# PNPdriver.net
KiCad netlist of a schematic drawn in Altium Designer
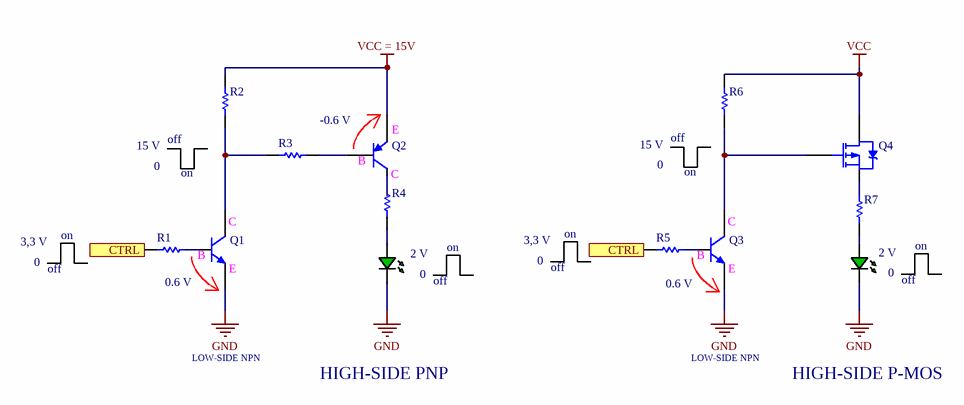
[diagram p0: PNPdriver.SchDoc]

(export (version "E")
  (design (tool "Eeschema 10.0.6"))
  (components
    (comp (ref "Q1")
      (value "2N3904")
      (footprint "TO-92A")
      (description "NPN General Purpose Amplifier")
      (fields (field (name "PUBLISHER") "Altium Limited"))
      (libsource (lib "Miscellaneous Devices") (part "2N3904"))
    )
    (comp (ref "Q2")
      (value "2N3906")
      (footprint "TO-92A")
      (description "PNP General Purpose Amplifier")
      (fields (field (name "PUBLISHER") "Altium Limited"))
      (libsource (lib "Miscellaneous Devices") (part "2N3906"))
    )
    (comp (ref "Q3")
      (value "2N3904")
      (footprint "TO-92A")
      (description "NPN General Purpose Amplifier")
      (fields (field (name "PUBLISHER") "Altium Limited"))
      (libsource (lib "Miscellaneous Devices") (part "2N3904"))
    )
    (comp (ref "Q4")
      (value "PMOS")
      (footprint "TO-220AB")
      (description "P-Channel Power MOSFET")
      (fields (field (name "PUBLISHER") "Altium Limited"))
      (libsource (lib "Miscellaneous Devices") (part "PMOS-2"))
    )
    (comp (ref "R1")
      (value "Res1")
      (footprint "AXIAL-0.3")
      (description "Resistor")
      (fields (field (name "PUBLISHER") "Altium Limited"))
      (libsource (lib "Miscellaneous Devices") (part "Res1"))
    )
    (comp (ref "R2")
      (value "Res1")
      (footprint "AXIAL-0.3")
      (description "Resistor")
      (fields (field (name "PUBLISHER") "Altium Limited"))
      (libsource (lib "Miscellaneous Devices") (part "Res1"))
    )
    (comp (ref "R3")
      (value "Res1")
      (footprint "AXIAL-0.3")
      (description "Resistor")
      (fields (field (name "PUBLISHER") "Altium Limited"))
      (libsource (lib "Miscellaneous Devices") (part "Res1"))
    )
    (comp (ref "R4")
      (value "Res1")
      (footprint "AXIAL-0.3")
      (description "Resistor")
      (fields (field (name "PUBLISHER") "Altium Limited"))
      (libsource (lib "Miscellaneous Devices") (part "Res1"))
    )
    (comp (ref "R5")
      (value "Res1")
      (footprint "AXIAL-0.3")
      (description "Resistor")
      (fields (field (name "PUBLISHER") "Altium Limited"))
      (libsource (lib "Miscellaneous Devices") (part "Res1"))
    )
    (comp (ref "R6")
      (value "Res1")
      (footprint "AXIAL-0.3")
      (description "Resistor")
      (fields (field (name "PUBLISHER") "Altium Limited"))
      (libsource (lib "Miscellaneous Devices") (part "Res1"))
    )
    (comp (ref "R7")
      (value "Res1")
      (footprint "AXIAL-0.3")
      (description "Resistor")
      (fields (field (name "PUBLISHER") "Altium Limited"))
      (libsource (lib "Miscellaneous Devices") (part "Res1"))
    )
    (comp (ref "TS-OFF1")
      (value "green")
      (footprint "3528_LED - duplicate1")
      (libsource (lib "all_in_one_library") (part "LEDG_0805"))
    )
    (comp (ref "TS-OFF2")
      (value "green")
      (footprint "3528_LED - duplicate1")
      (libsource (lib "all_in_one_library") (part "LEDG_0805"))
    )
  )
  (nets
    (net (code "1") (name "/CTRL") (class "Default")
      (node (ref "R1") (pin "2") (pinfunction "2_2") (pintype "passive"))
      (node (ref "R5") (pin "2") (pinfunction "2_2") (pintype "passive"))
    )
    (net (code "2") (name "GND") (class "Default")
      (node (ref "Q1") (pin "1") (pinfunction "E_1") (pintype "passive"))
      (node (ref "Q3") (pin "1") (pinfunction "E_1") (pintype "passive"))
      (node (ref "TS-OFF1") (pin "K") (pinfunction "K_K") (pintype "passive"))
      (node (ref "TS-OFF2") (pin "K") (pinfunction "K_K") (pintype "passive"))
    )
    (net (code "3") (name "Net-(Q1-B)") (class "Default")
      (node (ref "Q1") (pin "2") (pinfunction "B_2") (pintype "passive"))
      (node (ref "R1") (pin "1") (pinfunction "1_1") (pintype "passive"))
    )
    (net (code "4") (name "Net-(Q1-C)") (class "Default")
      (node (ref "Q1") (pin "3") (pinfunction "C_3") (pintype "passive"))
      (node (ref "R2") (pin "1") (pinfunction "1_1") (pintype "passive"))
      (node (ref "R3") (pin "2") (pinfunction "2_2") (pintype "passive"))
    )
    (net (code "5") (name "Net-(Q2-B)") (class "Default")
      (node (ref "Q2") (pin "2") (pinfunction "B_2") (pintype "passive"))
      (node (ref "R3") (pin "1") (pinfunction "1_1") (pintype "passive"))
    )
    (net (code "6") (name "Net-(Q2-C)") (class "Default")
      (node (ref "Q2") (pin "3") (pinfunction "C_3") (pintype "passive"))
      (node (ref "R4") (pin "2") (pinfunction "2_2") (pintype "passive"))
    )
    (net (code "7") (name "Net-(Q3-B)") (class "Default")
      (node (ref "Q3") (pin "2") (pinfunction "B_2") (pintype "passive"))
      (node (ref "R5") (pin "1") (pinfunction "1_1") (pintype "passive"))
    )
    (net (code "8") (name "Net-(Q3-C)") (class "Default")
      (node (ref "Q3") (pin "3") (pinfunction "C_3") (pintype "passive"))
      (node (ref "Q4") (pin "1") (pinfunction "G_1") (pintype "passive"))
      (node (ref "R6") (pin "2") (pinfunction "2_2") (pintype "passive"))
    )
    (net (code "9") (name "Net-(Q4-S)") (class "Default")
      (node (ref "Q4") (pin "3") (pinfunction "S_3") (pintype "passive"))
      (node (ref "R7") (pin "2") (pinfunction "2_2") (pintype "passive"))
    )
    (net (code "10") (name "Net-(R4-Pad1)") (class "Default")
      (node (ref "R4") (pin "1") (pinfunction "1_1") (pintype "passive"))
      (node (ref "TS-OFF1") (pin "A") (pinfunction "A_A") (pintype "passive"))
    )
    (net (code "11") (name "Net-(R7-Pad1)") (class "Default")
      (node (ref "R7") (pin "1") (pinfunction "1_1") (pintype "passive"))
      (node (ref "TS-OFF2") (pin "A") (pinfunction "A_A") (pintype "passive"))
    )
    (net (code "12") (name "VCC") (class "Default")
      (node (ref "Q4") (pin "2") (pinfunction "D_2") (pintype "passive"))
      (node (ref "R6") (pin "1") (pinfunction "1_1") (pintype "passive"))
    )
    (net (code "13") (name "VCC = 15V") (class "Default")
      (node (ref "Q2") (pin "1") (pinfunction "E_1") (pintype "passive"))
      (node (ref "R2") (pin "2") (pinfunction "2_2") (pintype "passive"))
    )
  )
)
